# PenMega.net
KiCad netlist of a schematic drawn in EAGLE
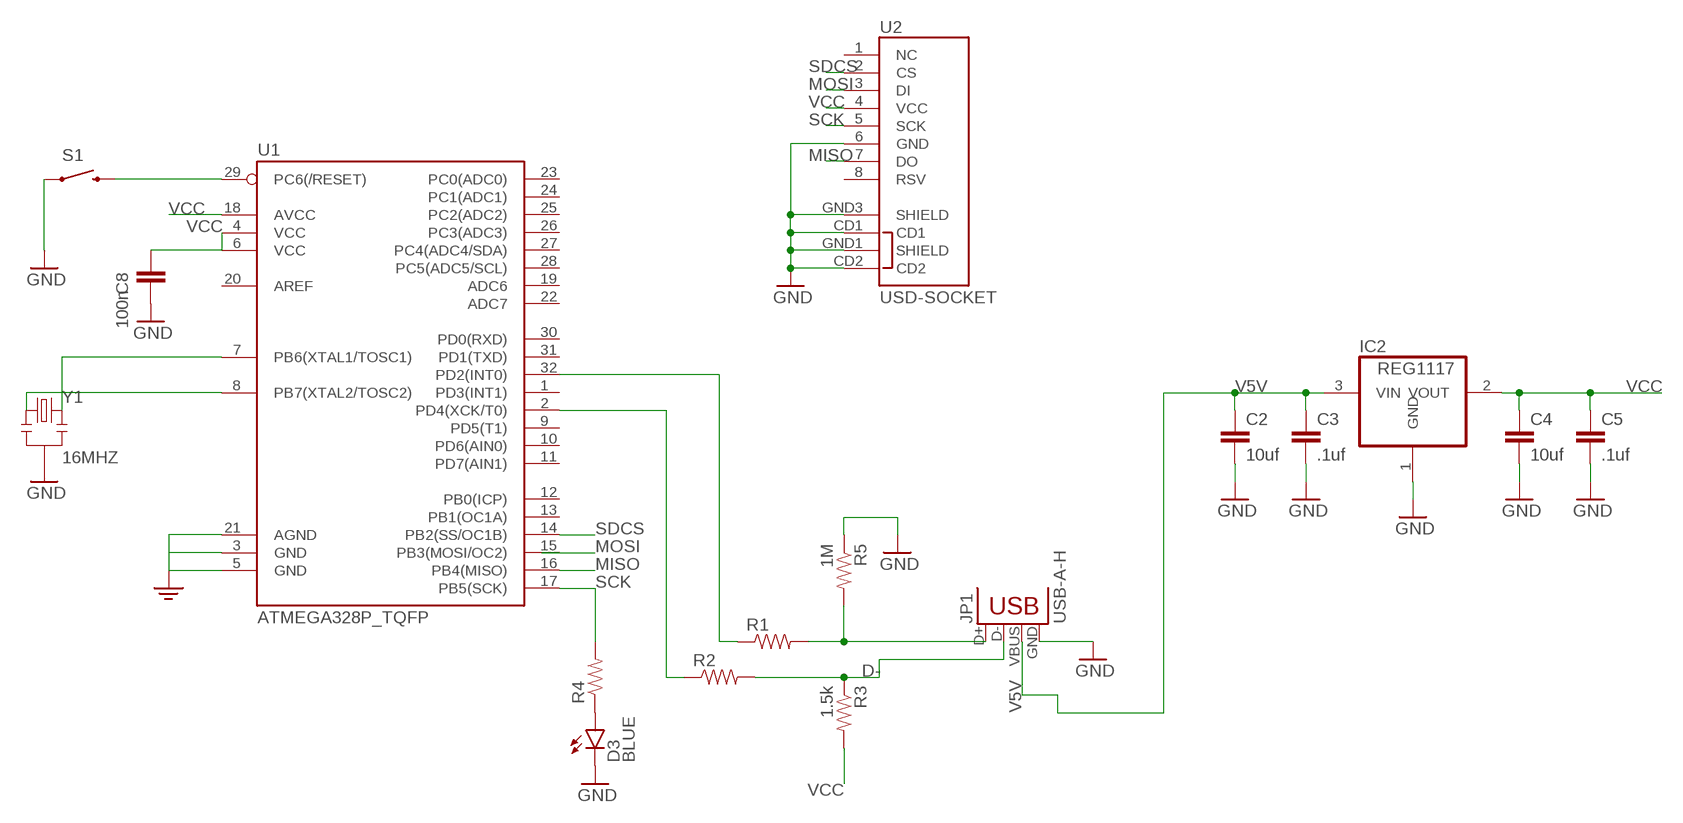
[diagram p0: schematic, sheet 1]

(export (version "E")
  (design (tool "Eeschema 10.0.6"))
  (components
    (comp (ref "C2")
      (value "10uf")
      (footprint "eagle-import:0805")
      (libsource (lib "eagle-import") (part "22UF-6.3V-20%(0805)"))
    )
    (comp (ref "C3")
      (value ".1uf")
      (footprint "eagle-import:0603-CAP")
      (libsource (lib "eagle-import") (part "CAP0603-CAP"))
    )
    (comp (ref "C4")
      (value "10uf")
      (footprint "eagle-import:0805")
      (libsource (lib "eagle-import") (part "22UF-6.3V-20%(0805)"))
    )
    (comp (ref "C5")
      (value ".1uf")
      (footprint "eagle-import:0603-CAP")
      (libsource (lib "eagle-import") (part "CAP0603-CAP"))
    )
    (comp (ref "C8")
      (value "100n")
      (footprint "eagle-import:0603-CAP")
      (libsource (lib "eagle-import") (part "CAP0603-CAP"))
    )
    (comp (ref "D3")
      (value "BLUE")
      (footprint "eagle-import:LED-0603")
      (libsource (lib "eagle-import") (part "LED-BLUE0603"))
    )
    (comp (ref "IC2")
      (value "REG1117")
      (footprint "eagle-import:SOT223")
      (libsource (lib "eagle-import") (part "REG1117"))
    )
    (comp (ref "JP1")
      (value "USB-A-H")
      (footprint "eagle-import:USB-A-H")
      (libsource (lib "eagle-import") (part "USB-A-H"))
    )
    (comp (ref "R1")
      (value "RESISTOR0603-RES")
      (footprint "eagle-import:0603-RES")
      (libsource (lib "eagle-import") (part "RESISTOR0603-RES"))
    )
    (comp (ref "R2")
      (value "RESISTOR0603-RES")
      (footprint "eagle-import:0603-RES")
      (libsource (lib "eagle-import") (part "RESISTOR0603-RES"))
    )
    (comp (ref "R3")
      (value "1.5k")
      (footprint "eagle-import:0603-RES")
      (libsource (lib "eagle-import") (part "RESISTOR0603-RES"))
    )
    (comp (ref "R4")
      (value "RESISTOR0603-RES")
      (footprint "eagle-import:0603-RES")
      (libsource (lib "eagle-import") (part "RESISTOR0603-RES"))
    )
    (comp (ref "R5")
      (value "1M")
      (footprint "eagle-import:0603-RES")
      (libsource (lib "eagle-import") (part "RESISTOR0603-RES"))
    )
    (comp (ref "S1")
      (value "SWITCH-MOMENTARY-2SMD")
      (footprint "eagle-import:TACTILE-SWITCH-SMD")
      (libsource (lib "eagle-import") (part "SWITCH-MOMENTARY-2SMD"))
    )
    (comp (ref "U1")
      (value "ATMEGA328P_TQFP")
      (footprint "eagle-import:TQFP32-08")
      (libsource (lib "eagle-import") (part "ATMEGA328P_TQFP"))
    )
    (comp (ref "U2")
      (value "USD-SOCKET")
      (footprint "eagle-import:MICROSD_1_1")
      (libsource (lib "eagle-import") (part "USD-SOCKET"))
    )
    (comp (ref "Y1")
      (value "16MHZ")
      (footprint "eagle-import:RESONATOR-SMD")
      (libsource (lib "eagle-import") (part "RESONATOR16MHZ"))
    )
  )
  (nets
    (net (code "1") (name "/D-") (class "Default")
      (node (ref "JP1") (pin "D-") (pinfunction "D-_D-") (pintype "bidirectional"))
      (node (ref "R2") (pin "2") (pinfunction "2_2") (pintype "passive"))
      (node (ref "R3") (pin "1") (pinfunction "1_1") (pintype "passive"))
    )
    (net (code "2") (name "/MISO") (class "Default")
      (node (ref "U1") (pin "16") (pinfunction "PB4(MISO)_16") (pintype "bidirectional"))
      (node (ref "U2") (pin "7") (pinfunction "DO_7") (pintype "bidirectional"))
    )
    (net (code "3") (name "/MOSI") (class "Default")
      (node (ref "U2") (pin "3") (pinfunction "DI_3") (pintype "bidirectional"))
    )
    (net (code "4") (name "/SCK") (class "Default")
      (node (ref "R4") (pin "2") (pinfunction "2_2") (pintype "passive"))
      (node (ref "U1") (pin "17") (pinfunction "PB5(SCK)_17") (pintype "bidirectional"))
      (node (ref "U2") (pin "5") (pinfunction "SCK_5") (pintype "bidirectional"))
    )
    (net (code "5") (name "/SDCS") (class "Default")
      (node (ref "U1") (pin "14") (pinfunction "PB2(SS/OC1B)_14") (pintype "bidirectional"))
      (node (ref "U2") (pin "2") (pinfunction "CS_2") (pintype "bidirectional"))
    )
    (net (code "6") (name "/V5V") (class "Default")
      (node (ref "C2") (pin "1") (pinfunction "1_1") (pintype "passive"))
      (node (ref "C3") (pin "1") (pinfunction "1_1") (pintype "passive"))
      (node (ref "IC2") (pin "3") (pinfunction "VIN_3") (pintype "input"))
      (node (ref "JP1") (pin "VBUS") (pinfunction "VBUS_VBUS") (pintype "bidirectional"))
    )
    (net (code "7") (name "/VCC") (class "Default")
      (node (ref "C4") (pin "1") (pinfunction "1_1") (pintype "passive"))
      (node (ref "C5") (pin "1") (pinfunction "1_1") (pintype "passive"))
      (node (ref "C8") (pin "1") (pinfunction "1_1") (pintype "passive"))
      (node (ref "IC2") (pin "2") (pinfunction "VOUT_2") (pintype "output"))
      (node (ref "R3") (pin "2") (pinfunction "2_2") (pintype "passive"))
      (node (ref "U1") (pin "18") (pinfunction "AVCC_18") (pintype "bidirectional"))
      (node (ref "U1") (pin "4") (pinfunction "VCC_4") (pintype "bidirectional"))
      (node (ref "U1") (pin "6") (pinfunction "VCC_6") (pintype "bidirectional"))
      (node (ref "U2") (pin "4") (pinfunction "VCC_4") (pintype "bidirectional"))
    )
    (net (code "8") (name "GND") (class "Default")
      (node (ref "C2") (pin "2") (pinfunction "2_2") (pintype "passive"))
      (node (ref "C3") (pin "2") (pinfunction "2_2") (pintype "passive"))
      (node (ref "C4") (pin "2") (pinfunction "2_2") (pintype "passive"))
      (node (ref "C5") (pin "2") (pinfunction "2_2") (pintype "passive"))
      (node (ref "C8") (pin "2") (pinfunction "2_2") (pintype "passive"))
      (node (ref "D3") (pin "C") (pinfunction "C_C") (pintype "passive"))
      (node (ref "IC2") (pin "1") (pinfunction "GND_1") (pintype "power_in"))
      (node (ref "JP1") (pin "GND") (pinfunction "GND_GND") (pintype "bidirectional"))
      (node (ref "R5") (pin "1") (pinfunction "1_1") (pintype "passive"))
      (node (ref "S1") (pin "1") (pinfunction "1_1") (pintype "passive"))
      (node (ref "U1") (pin "21") (pinfunction "AGND_21") (pintype "bidirectional"))
      (node (ref "U1") (pin "3") (pinfunction "GND_3") (pintype "bidirectional"))
      (node (ref "U1") (pin "5") (pinfunction "GND_5") (pintype "bidirectional"))
      (node (ref "U2") (pin "6") (pinfunction "GND_6") (pintype "bidirectional"))
      (node (ref "U2") (pin "CD1") (pinfunction "CD1_CD1") (pintype "bidirectional"))
      (node (ref "U2") (pin "CD2") (pinfunction "CD2_CD2") (pintype "bidirectional"))
      (node (ref "U2") (pin "GND1") (pinfunction "SHIELD_GND1") (pintype "bidirectional"))
      (node (ref "U2") (pin "GND3") (pinfunction "SHIELD_GND3") (pintype "bidirectional"))
      (node (ref "Y1") (pin "2") (pinfunction "2_2") (pintype "passive"))
    )
    (net (code "9") (name "Net-(D3-PadA)") (class "Default")
      (node (ref "D3") (pin "A") (pinfunction "A_A") (pintype "passive"))
      (node (ref "R4") (pin "1") (pinfunction "1_1") (pintype "passive"))
    )
    (net (code "10") (name "Net-(JP1-PadD+)") (class "Default")
      (node (ref "JP1") (pin "D+") (pinfunction "D+_D+") (pintype "bidirectional"))
      (node (ref "R1") (pin "2") (pinfunction "2_2") (pintype "passive"))
      (node (ref "R5") (pin "2") (pinfunction "2_2") (pintype "passive"))
    )
    (net (code "11") (name "Net-(S1-2)") (class "Default")
      (node (ref "S1") (pin "3") (pinfunction "2_3") (pintype "passive"))
      (node (ref "U1") (pin "29") (pinfunction "PC6(/RESET)_29") (pintype "bidirectional"))
    )
    (net (code "12") (name "Net-(U1-PB6(XTAL1{slash}TOSC1))") (class "Default")
      (node (ref "U1") (pin "7") (pinfunction "PB6(XTAL1/TOSC1)_7") (pintype "bidirectional"))
      (node (ref "Y1") (pin "3") (pinfunction "3_3") (pintype "passive"))
    )
    (net (code "13") (name "Net-(U1-PB7(XTAL2{slash}TOSC2))") (class "Default")
      (node (ref "U1") (pin "8") (pinfunction "PB7(XTAL2/TOSC2)_8") (pintype "bidirectional"))
      (node (ref "Y1") (pin "1") (pinfunction "1_1") (pintype "passive"))
    )
    (net (code "14") (name "Net-(U1-PD2(INT0))") (class "Default")
      (node (ref "R1") (pin "1") (pinfunction "1_1") (pintype "passive"))
      (node (ref "U1") (pin "32") (pinfunction "PD2(INT0)_32") (pintype "bidirectional"))
    )
    (net (code "15") (name "Net-(U1-PD4(XCK{slash}T0))") (class "Default")
      (node (ref "R2") (pin "1") (pinfunction "1_1") (pintype "passive"))
      (node (ref "U1") (pin "2") (pinfunction "PD4(XCK/T0)_2") (pintype "bidirectional"))
    )
    (net (code "16") (name "unconnected-(U1-ADC6-Pad19)") (class "Default")
      (node (ref "U1") (pin "19") (pinfunction "ADC6_19") (pintype "bidirectional"))
    )
    (net (code "17") (name "unconnected-(U1-ADC7-Pad22)") (class "Default")
      (node (ref "U1") (pin "22") (pinfunction "ADC7_22") (pintype "bidirectional"))
    )
    (net (code "18") (name "unconnected-(U1-AREF-Pad20)") (class "Default")
      (node (ref "U1") (pin "20") (pinfunction "AREF_20") (pintype "bidirectional"))
    )
    (net (code "19") (name "unconnected-(U1-PB0(ICP)-Pad12)") (class "Default")
      (node (ref "U1") (pin "12") (pinfunction "PB0(ICP)_12") (pintype "bidirectional"))
    )
    (net (code "20") (name "unconnected-(U1-PB1(OC1A)-Pad13)") (class "Default")
      (node (ref "U1") (pin "13") (pinfunction "PB1(OC1A)_13") (pintype "bidirectional"))
    )
    (net (code "21") (name "unconnected-(U1-PB3(MOSI{slash}OC2)-Pad15)") (class "Default")
      (node (ref "U1") (pin "15") (pinfunction "PB3(MOSI/OC2)_15") (pintype "bidirectional"))
    )
    (net (code "22") (name "unconnected-(U1-PC0(ADC0)-Pad23)") (class "Default")
      (node (ref "U1") (pin "23") (pinfunction "PC0(ADC0)_23") (pintype "bidirectional"))
    )
    (net (code "23") (name "unconnected-(U1-PC1(ADC1)-Pad24)") (class "Default")
      (node (ref "U1") (pin "24") (pinfunction "PC1(ADC1)_24") (pintype "bidirectional"))
    )
    (net (code "24") (name "unconnected-(U1-PC2(ADC2)-Pad25)") (class "Default")
      (node (ref "U1") (pin "25") (pinfunction "PC2(ADC2)_25") (pintype "bidirectional"))
    )
    (net (code "25") (name "unconnected-(U1-PC3(ADC3)-Pad26)") (class "Default")
      (node (ref "U1") (pin "26") (pinfunction "PC3(ADC3)_26") (pintype "bidirectional"))
    )
    (net (code "26") (name "unconnected-(U1-PC4(ADC4{slash}SDA)-Pad27)") (class "Default")
      (node (ref "U1") (pin "27") (pinfunction "PC4(ADC4/SDA)_27") (pintype "bidirectional"))
    )
    (net (code "27") (name "unconnected-(U1-PC5(ADC5{slash}SCL)-Pad28)") (class "Default")
      (node (ref "U1") (pin "28") (pinfunction "PC5(ADC5/SCL)_28") (pintype "bidirectional"))
    )
    (net (code "28") (name "unconnected-(U1-PD0(RXD)-Pad30)") (class "Default")
      (node (ref "U1") (pin "30") (pinfunction "PD0(RXD)_30") (pintype "bidirectional"))
    )
    (net (code "29") (name "unconnected-(U1-PD1(TXD)-Pad31)") (class "Default")
      (node (ref "U1") (pin "31") (pinfunction "PD1(TXD)_31") (pintype "bidirectional"))
    )
    (net (code "30") (name "unconnected-(U1-PD3(INT1)-Pad1)") (class "Default")
      (node (ref "U1") (pin "1") (pinfunction "PD3(INT1)_1") (pintype "bidirectional"))
    )
    (net (code "31") (name "unconnected-(U1-PD5(T1)-Pad9)") (class "Default")
      (node (ref "U1") (pin "9") (pinfunction "PD5(T1)_9") (pintype "bidirectional"))
    )
    (net (code "32") (name "unconnected-(U1-PD6(AIN0)-Pad10)") (class "Default")
      (node (ref "U1") (pin "10") (pinfunction "PD6(AIN0)_10") (pintype "bidirectional"))
    )
    (net (code "33") (name "unconnected-(U1-PD7(AIN1)-Pad11)") (class "Default")
      (node (ref "U1") (pin "11") (pinfunction "PD7(AIN1)_11") (pintype "bidirectional"))
    )
    (net (code "34") (name "unconnected-(U2-NC-Pad1)") (class "Default")
      (node (ref "U2") (pin "1") (pinfunction "NC_1") (pintype "bidirectional"))
    )
    (net (code "35") (name "unconnected-(U2-RSV-Pad8)") (class "Default")
      (node (ref "U2") (pin "8") (pinfunction "RSV_8") (pintype "bidirectional"))
    )
  )
)
